# 06-multimodal-microcontroller.net
KiCad netlist of a schematic drawn in Altium Designer
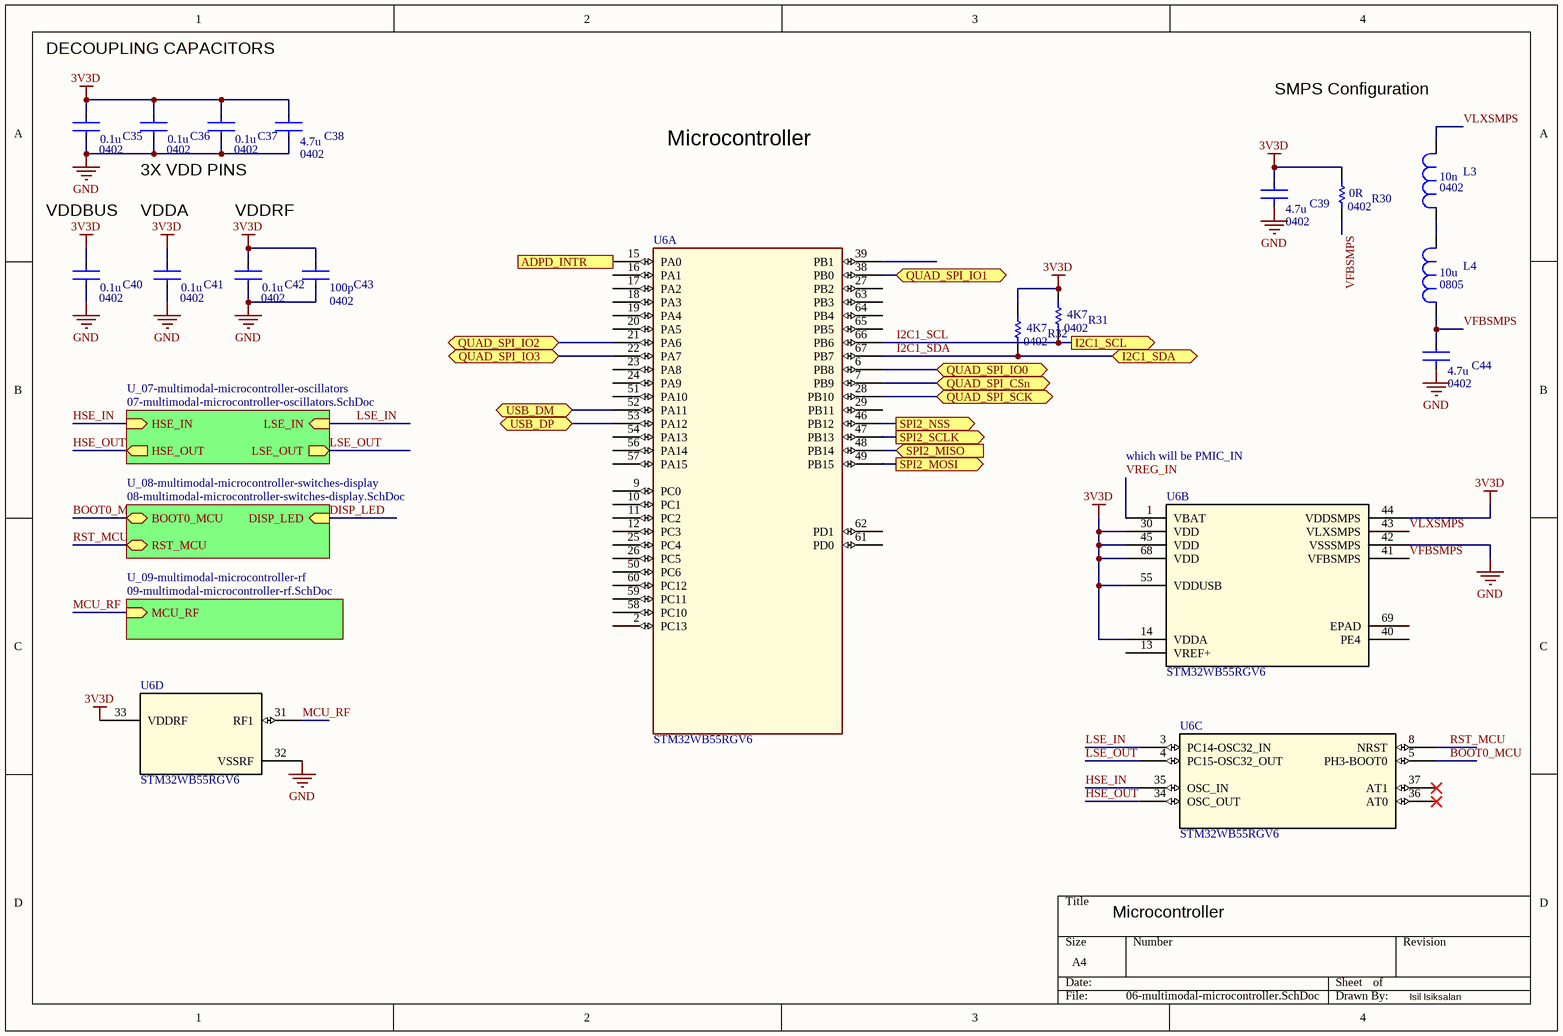
[diagram p0: 06-multimodal-microcontroller.SchDoc]

(export (version "E")
  (design (tool "Eeschema 10.0.6"))
  (components
    (comp (ref "C35")
      (value "C1005X7R1H104K050BB")
      (footprint "CAPTDK0402")
      (description "CAP CER 0.1UF 50V X7R 0402")
      (libsource (lib "multimodal") (part "C1005X7R1H104K050BB"))
    )
    (comp (ref "C36")
      (value "C1005X7R1H104K050BB")
      (footprint "CAPTDK0402")
      (description "CAP CER 0.1UF 50V X7R 0402")
      (libsource (lib "multimodal") (part "C1005X7R1H104K050BB"))
    )
    (comp (ref "C37")
      (value "C1005X7R1H104K050BB")
      (footprint "CAPTDK0402")
      (description "CAP CER 0.1UF 50V X7R 0402")
      (libsource (lib "multimodal") (part "C1005X7R1H104K050BB"))
    )
    (comp (ref "C38")
      (value "C1005X5R1A475K050BC")
      (footprint "CAPTDK0402")
      (description "CAP CER 4.7UF 10V X5R 0402")
      (libsource (lib "multimodal") (part "C1005X5R1A475K050BC"))
    )
    (comp (ref "C39")
      (value "C1005X5R1A475K050BC")
      (footprint "CAPTDK0402")
      (description "CAP CER 4.7UF 10V X5R 0402")
      (libsource (lib "multimodal") (part "C1005X5R1A475K050BC"))
    )
    (comp (ref "C40")
      (value "C1005X7R1H104K050BB")
      (footprint "CAPTDK0402")
      (description "CAP CER 0.1UF 50V X7R 0402")
      (libsource (lib "multimodal") (part "C1005X7R1H104K050BB"))
    )
    (comp (ref "C41")
      (value "C1005X7R1H104K050BB")
      (footprint "CAPTDK0402")
      (description "CAP CER 0.1UF 50V X7R 0402")
      (libsource (lib "multimodal") (part "C1005X7R1H104K050BB"))
    )
    (comp (ref "C42")
      (value "C1005X7R1H104K050BB")
      (footprint "CAPTDK0402")
      (description "CAP CER 0.1UF 50V X7R 0402")
      (libsource (lib "multimodal") (part "C1005X7R1H104K050BB"))
    )
    (comp (ref "C43")
      (value "CGA2B2C0G1H101J050BA")
      (footprint "CAPTDK0402")
      (description "CAP CER 100PF 50V C0G 0402")
      (libsource (lib "multimodal") (part "CGA2B2C0G1H101J050BA_1"))
    )
    (comp (ref "C44")
      (value "C1005X5R1A475K050BC")
      (footprint "CAPTDK0402")
      (description "CAP CER 4.7UF 10V X5R 0402")
      (libsource (lib "multimodal") (part "C1005X5R1A475K050BC"))
    )
    (comp (ref "L3")
      (value "LQG15WZ10NJ02D")
      (footprint "INDMURT0402")
      (description "FIXED IND 10NH 500MA 190MOHM SMD")
      (libsource (lib "multimodal") (part "LQG15WZ10NJ02D"))
    )
    (comp (ref "L4")
      (value "LQM21FN100N00L")
      (footprint "INDMURT0805")
      (description "FIXED IND 10UH 60MA 650 MOHM SMD")
      (libsource (lib "multimodal") (part "LQM21FN100N00L"))
    )
    (comp (ref "R30")
      (value "RMCF0402ZT0R00")
      (footprint "RES-STACK-POLE-0402")
      (description "RES 0 OHM JUMPER 1/16W 0402")
      (libsource (lib "multimodal") (part "RMCF0402ZT0R00"))
    )
    (comp (ref "R31")
      (value "RMCF0402FT4K70")
      (footprint "RES-STACK-POLE-0402")
      (description "RES 4.7K OHM 1% 1/16W 0402")
      (libsource (lib "multimodal") (part "RMCF0402FT4K70"))
    )
    (comp (ref "R32")
      (value "RMCF0402FT4K70")
      (footprint "RES-STACK-POLE-0402")
      (description "RES 4.7K OHM 1% 1/16W 0402")
      (libsource (lib "multimodal") (part "RMCF0402FT4K70"))
    )
    (comp (ref "U6")
      (value "STM32WB55RGV6")
      (footprint "STM32WB55RG")
      (fields (field (name "COPYRIGHT") "Copyright (C) 2025 Ultra Librarian. All rights reserved."))
      (libsource (lib "multimodal") (part "STM32WB55RGV6"))
    )
  )
  (nets
    (net (code "1") (name "/ADPD_INTR") (class "Default")
      (node (ref "U6") (pin "15") (pinfunction "PA0_15") (pintype "bidirectional"))
    )
    (net (code "2") (name "/BOOT0_MCU") (class "Default")
      (node (ref "U6") (pin "5") (pinfunction "PH3-BOOT0_5") (pintype "bidirectional"))
    )
    (net (code "4") (name "/HSE_IN") (class "Default")
      (node (ref "U6") (pin "35") (pinfunction "OSC_IN_35") (pintype "bidirectional"))
    )
    (net (code "5") (name "/HSE_OUT") (class "Default")
      (node (ref "U6") (pin "34") (pinfunction "OSC_OUT_34") (pintype "bidirectional"))
    )
    (net (code "6") (name "/I2C1_SCL") (class "Default")
      (node (ref "R31") (pin "1") (pinfunction "1_1") (pintype "passive"))
      (node (ref "U6") (pin "66") (pinfunction "PB6_66") (pintype "bidirectional"))
    )
    (net (code "7") (name "/I2C1_SDA") (class "Default")
      (node (ref "R32") (pin "1") (pinfunction "1_1") (pintype "passive"))
      (node (ref "U6") (pin "67") (pinfunction "PB7_67") (pintype "bidirectional"))
    )
    (net (code "8") (name "/LSE_IN") (class "Default")
      (node (ref "U6") (pin "3") (pinfunction "PC14-OSC32_IN_3") (pintype "bidirectional"))
    )
    (net (code "9") (name "/LSE_OUT") (class "Default")
      (node (ref "U6") (pin "4") (pinfunction "PC15-OSC32_OUT_4") (pintype "bidirectional"))
    )
    (net (code "10") (name "/MCU_RF") (class "Default")
      (node (ref "U6") (pin "31") (pinfunction "RF1_31") (pintype "bidirectional"))
    )
    (net (code "11") (name "/QUAD_SPI_CSn") (class "Default")
      (node (ref "U6") (pin "7") (pinfunction "PB9_7") (pintype "bidirectional"))
    )
    (net (code "12") (name "/QUAD_SPI_IO0") (class "Default")
      (node (ref "U6") (pin "6") (pinfunction "PB8_6") (pintype "bidirectional"))
    )
    (net (code "13") (name "/QUAD_SPI_IO1") (class "Default")
      (node (ref "U6") (pin "38") (pinfunction "PB0_38") (pintype "bidirectional"))
    )
    (net (code "14") (name "/QUAD_SPI_IO2") (class "Default")
      (node (ref "U6") (pin "21") (pinfunction "PA6_21") (pintype "bidirectional"))
    )
    (net (code "15") (name "/QUAD_SPI_IO3") (class "Default")
      (node (ref "U6") (pin "22") (pinfunction "PA7_22") (pintype "bidirectional"))
    )
    (net (code "16") (name "/QUAD_SPI_SCK") (class "Default")
      (node (ref "U6") (pin "28") (pinfunction "PB10_28") (pintype "bidirectional"))
    )
    (net (code "17") (name "/RST_MCU") (class "Default")
      (node (ref "U6") (pin "8") (pinfunction "NRST_8") (pintype "bidirectional"))
    )
    (net (code "18") (name "/SPI2_MISO") (class "Default")
      (node (ref "U6") (pin "48") (pinfunction "PB14_48") (pintype "bidirectional"))
    )
    (net (code "19") (name "/SPI2_MOSI") (class "Default")
      (node (ref "U6") (pin "49") (pinfunction "PB15_49") (pintype "bidirectional"))
    )
    (net (code "20") (name "/SPI2_NSS") (class "Default")
      (node (ref "U6") (pin "46") (pinfunction "PB12_46") (pintype "bidirectional"))
    )
    (net (code "21") (name "/SPI2_SCLK") (class "Default")
      (node (ref "U6") (pin "47") (pinfunction "PB13_47") (pintype "bidirectional"))
    )
    (net (code "22") (name "/USB_DM") (class "Default")
      (node (ref "U6") (pin "52") (pinfunction "PA11_52") (pintype "bidirectional"))
    )
    (net (code "23") (name "/USB_DP") (class "Default")
      (node (ref "U6") (pin "53") (pinfunction "PA12_53") (pintype "bidirectional"))
    )
    (net (code "24") (name "/VFBSMPS") (class "Default")
      (node (ref "C44") (pin "1") (pinfunction "1_1") (pintype "passive"))
      (node (ref "L4") (pin "2") (pinfunction "2_2") (pintype "passive"))
      (node (ref "R30") (pin "1") (pinfunction "1_1") (pintype "passive"))
      (node (ref "U6") (pin "41") (pinfunction "VFBSMPS_41") (pintype "power_in"))
    )
    (net (code "25") (name "/VLXSMPS") (class "Default")
      (node (ref "L3") (pin "1") (pinfunction "1_1") (pintype "passive"))
      (node (ref "U6") (pin "43") (pinfunction "VLXSMPS_43") (pintype "power_in"))
    )
    (net (code "26") (name "/VREG_IN") (class "Default")
      (node (ref "U6") (pin "1") (pinfunction "VBAT_1") (pintype "power_in"))
    )
    (net (code "27") (name "3V3D") (class "Default")
      (node (ref "C35") (pin "1") (pinfunction "1_1") (pintype "passive"))
      (node (ref "C36") (pin "1") (pinfunction "1_1") (pintype "passive"))
      (node (ref "C37") (pin "1") (pinfunction "1_1") (pintype "passive"))
      (node (ref "C38") (pin "1") (pinfunction "1_1") (pintype "passive"))
      (node (ref "C39") (pin "1") (pinfunction "1_1") (pintype "passive"))
      (node (ref "C40") (pin "1") (pinfunction "1_1") (pintype "passive"))
      (node (ref "C41") (pin "1") (pinfunction "1_1") (pintype "passive"))
      (node (ref "C42") (pin "1") (pinfunction "1_1") (pintype "passive"))
      (node (ref "C43") (pin "1") (pinfunction "1_1") (pintype "passive"))
      (node (ref "R30") (pin "2") (pinfunction "2_2") (pintype "passive"))
      (node (ref "R31") (pin "2") (pinfunction "2_2") (pintype "passive"))
      (node (ref "R32") (pin "2") (pinfunction "2_2") (pintype "passive"))
      (node (ref "U6") (pin "14") (pinfunction "VDDA_14") (pintype "power_in"))
      (node (ref "U6") (pin "30") (pinfunction "VDD_30") (pintype "power_in"))
      (node (ref "U6") (pin "33") (pinfunction "VDDRF_33") (pintype "power_in"))
      (node (ref "U6") (pin "44") (pinfunction "VDDSMPS_44") (pintype "power_in"))
      (node (ref "U6") (pin "45") (pinfunction "VDD_45") (pintype "power_in"))
      (node (ref "U6") (pin "55") (pinfunction "VDDUSB_55") (pintype "power_in"))
      (node (ref "U6") (pin "68") (pinfunction "VDD_68") (pintype "power_in"))
    )
    (net (code "28") (name "GND") (class "Default")
      (node (ref "C35") (pin "2") (pinfunction "2_2") (pintype "passive"))
      (node (ref "C36") (pin "2") (pinfunction "2_2") (pintype "passive"))
      (node (ref "C37") (pin "2") (pinfunction "2_2") (pintype "passive"))
      (node (ref "C38") (pin "2") (pinfunction "2_2") (pintype "passive"))
      (node (ref "C39") (pin "2") (pinfunction "2_2") (pintype "passive"))
      (node (ref "C40") (pin "2") (pinfunction "2_2") (pintype "passive"))
      (node (ref "C41") (pin "2") (pinfunction "2_2") (pintype "passive"))
      (node (ref "C42") (pin "2") (pinfunction "2_2") (pintype "passive"))
      (node (ref "C43") (pin "2") (pinfunction "2_2") (pintype "passive"))
      (node (ref "C44") (pin "2") (pinfunction "2_2") (pintype "passive"))
      (node (ref "U6") (pin "32") (pinfunction "VSSRF_32") (pintype "power_in"))
      (node (ref "U6") (pin "42") (pinfunction "VSSSMPS_42") (pintype "power_in"))
    )
    (net (code "29") (name "Net-(L3-Pad2)") (class "Default")
      (node (ref "L3") (pin "2") (pinfunction "2_2") (pintype "passive"))
      (node (ref "L4") (pin "1") (pinfunction "1_1") (pintype "passive"))
    )
    (net (code "30") (name "unconnected-(U6A-PA1-Pad16)") (class "Default")
      (node (ref "U6") (pin "16") (pinfunction "PA1_16") (pintype "bidirectional"))
    )
    (net (code "31") (name "unconnected-(U6A-PA2-Pad17)") (class "Default")
      (node (ref "U6") (pin "17") (pinfunction "PA2_17") (pintype "bidirectional"))
    )
    (net (code "32") (name "unconnected-(U6A-PA3-Pad18)") (class "Default")
      (node (ref "U6") (pin "18") (pinfunction "PA3_18") (pintype "bidirectional"))
    )
    (net (code "33") (name "unconnected-(U6A-PA4-Pad19)") (class "Default")
      (node (ref "U6") (pin "19") (pinfunction "PA4_19") (pintype "bidirectional"))
    )
    (net (code "34") (name "unconnected-(U6A-PA5-Pad20)") (class "Default")
      (node (ref "U6") (pin "20") (pinfunction "PA5_20") (pintype "bidirectional"))
    )
    (net (code "35") (name "unconnected-(U6A-PA8-Pad23)") (class "Default")
      (node (ref "U6") (pin "23") (pinfunction "PA8_23") (pintype "bidirectional"))
    )
    (net (code "36") (name "unconnected-(U6A-PA9-Pad24)") (class "Default")
      (node (ref "U6") (pin "24") (pinfunction "PA9_24") (pintype "bidirectional"))
    )
    (net (code "37") (name "unconnected-(U6A-PA10-Pad51)") (class "Default")
      (node (ref "U6") (pin "51") (pinfunction "PA10_51") (pintype "bidirectional"))
    )
    (net (code "38") (name "unconnected-(U6A-PA13-Pad54)") (class "Default")
      (node (ref "U6") (pin "54") (pinfunction "PA13_54") (pintype "bidirectional"))
    )
    (net (code "39") (name "unconnected-(U6A-PA14-Pad56)") (class "Default")
      (node (ref "U6") (pin "56") (pinfunction "PA14_56") (pintype "bidirectional"))
    )
    (net (code "40") (name "unconnected-(U6A-PA15-Pad57)") (class "Default")
      (node (ref "U6") (pin "57") (pinfunction "PA15_57") (pintype "bidirectional"))
    )
    (net (code "41") (name "unconnected-(U6A-PB1-Pad39)") (class "Default")
      (node (ref "U6") (pin "39") (pinfunction "PB1_39") (pintype "bidirectional"))
    )
    (net (code "42") (name "unconnected-(U6A-PB2-Pad27)") (class "Default")
      (node (ref "U6") (pin "27") (pinfunction "PB2_27") (pintype "bidirectional"))
    )
    (net (code "43") (name "unconnected-(U6A-PB3-Pad63)") (class "Default")
      (node (ref "U6") (pin "63") (pinfunction "PB3_63") (pintype "bidirectional"))
    )
    (net (code "44") (name "unconnected-(U6A-PB4-Pad64)") (class "Default")
      (node (ref "U6") (pin "64") (pinfunction "PB4_64") (pintype "bidirectional"))
    )
    (net (code "45") (name "unconnected-(U6A-PB5-Pad65)") (class "Default")
      (node (ref "U6") (pin "65") (pinfunction "PB5_65") (pintype "bidirectional"))
    )
    (net (code "46") (name "unconnected-(U6A-PB11-Pad29)") (class "Default")
      (node (ref "U6") (pin "29") (pinfunction "PB11_29") (pintype "bidirectional"))
    )
    (net (code "47") (name "unconnected-(U6A-PC0-Pad9)") (class "Default")
      (node (ref "U6") (pin "9") (pinfunction "PC0_9") (pintype "bidirectional"))
    )
    (net (code "48") (name "unconnected-(U6A-PC1-Pad10)") (class "Default")
      (node (ref "U6") (pin "10") (pinfunction "PC1_10") (pintype "bidirectional"))
    )
    (net (code "49") (name "unconnected-(U6A-PC2-Pad11)") (class "Default")
      (node (ref "U6") (pin "11") (pinfunction "PC2_11") (pintype "bidirectional"))
    )
    (net (code "50") (name "unconnected-(U6A-PC3-Pad12)") (class "Default")
      (node (ref "U6") (pin "12") (pinfunction "PC3_12") (pintype "bidirectional"))
    )
    (net (code "51") (name "unconnected-(U6A-PC4-Pad25)") (class "Default")
      (node (ref "U6") (pin "25") (pinfunction "PC4_25") (pintype "bidirectional"))
    )
    (net (code "52") (name "unconnected-(U6A-PC5-Pad26)") (class "Default")
      (node (ref "U6") (pin "26") (pinfunction "PC5_26") (pintype "bidirectional"))
    )
    (net (code "53") (name "unconnected-(U6A-PC6-Pad50)") (class "Default")
      (node (ref "U6") (pin "50") (pinfunction "PC6_50") (pintype "bidirectional"))
    )
    (net (code "54") (name "unconnected-(U6A-PC10-Pad58)") (class "Default")
      (node (ref "U6") (pin "58") (pinfunction "PC10_58") (pintype "bidirectional"))
    )
    (net (code "55") (name "unconnected-(U6A-PC11-Pad59)") (class "Default")
      (node (ref "U6") (pin "59") (pinfunction "PC11_59") (pintype "bidirectional"))
    )
    (net (code "56") (name "unconnected-(U6A-PC12-Pad60)") (class "Default")
      (node (ref "U6") (pin "60") (pinfunction "PC12_60") (pintype "bidirectional"))
    )
    (net (code "57") (name "unconnected-(U6A-PC13-Pad2)") (class "Default")
      (node (ref "U6") (pin "2") (pinfunction "PC13_2") (pintype "bidirectional"))
    )
    (net (code "58") (name "unconnected-(U6A-PD0-Pad61)") (class "Default")
      (node (ref "U6") (pin "61") (pinfunction "PD0_61") (pintype "bidirectional"))
    )
    (net (code "59") (name "unconnected-(U6A-PD1-Pad62)") (class "Default")
      (node (ref "U6") (pin "62") (pinfunction "PD1_62") (pintype "bidirectional"))
    )
    (net (code "60") (name "unconnected-(U6B-EPAD-Pad69)") (class "Default")
      (node (ref "U6") (pin "69") (pinfunction "EPAD_69") (pintype "power_in"))
    )
    (net (code "61") (name "unconnected-(U6B-PE4-Pad40)") (class "Default")
      (node (ref "U6") (pin "40") (pinfunction "PE4_40") (pintype "power_in"))
    )
    (net (code "62") (name "unconnected-(U6B-VREF+-Pad13)") (class "Default")
      (node (ref "U6") (pin "13") (pinfunction "VREF+_13") (pintype "power_in"))
    )
    (net (code "63") (name "unconnected-(U6C-AT0-Pad36)") (class "Default")
      (node (ref "U6") (pin "36") (pinfunction "AT0_36") (pintype "bidirectional+no_connect"))
    )
    (net (code "64") (name "unconnected-(U6C-AT1-Pad37)") (class "Default")
      (node (ref "U6") (pin "37") (pinfunction "AT1_37") (pintype "bidirectional+no_connect"))
    )
  )
)
